# Power.net
KiCad netlist of a schematic drawn in Altium Designer
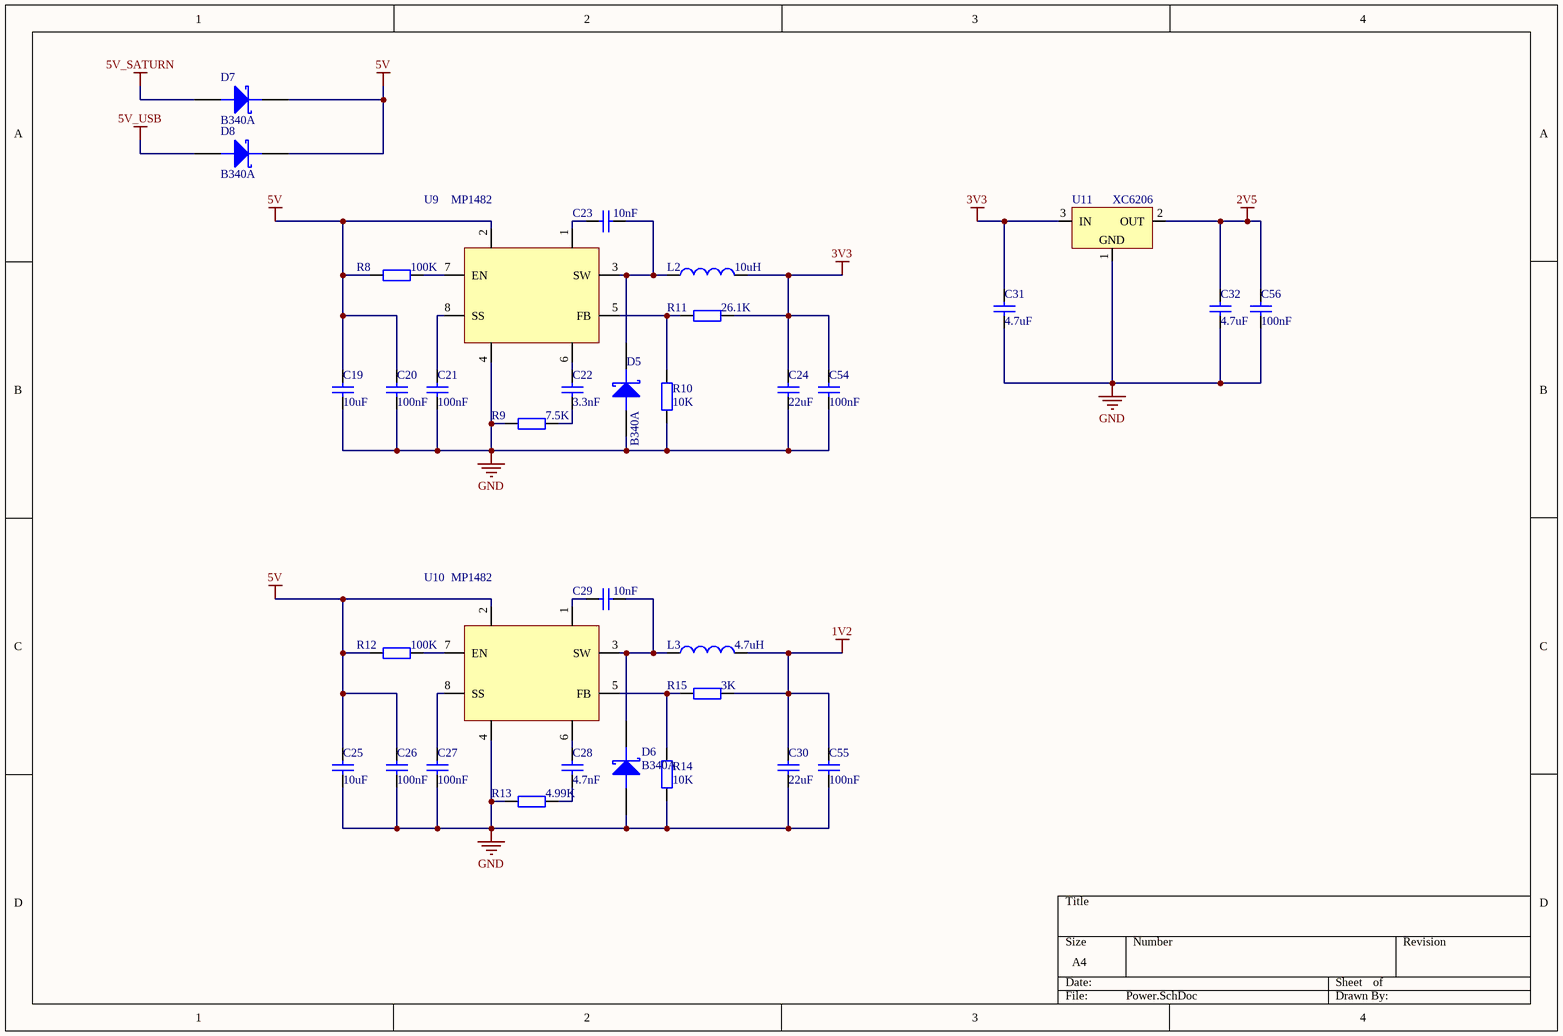
[diagram p0: Power.SchDoc]

(export (version "E")
  (design (tool "Eeschema 10.0.6"))
  (components
    (comp (ref "C19")
      (value "10uF")
      (footprint "C1206")
      (description "Capacitor")
      (fields (field (name "PUBLISHER") "Altium Limited"))
      (libsource (lib "Miscellaneous Devices") (part "Cap"))
    )
    (comp (ref "C20")
      (value "100nF")
      (footprint "C0603")
      (description "Capacitor")
      (fields (field (name "PUBLISHER") "Altium Limited"))
      (libsource (lib "Miscellaneous Devices") (part "Cap"))
    )
    (comp (ref "C21")
      (value "100nF")
      (footprint "C0603")
      (description "Capacitor")
      (fields (field (name "PUBLISHER") "Altium Limited"))
      (libsource (lib "Miscellaneous Devices") (part "Cap"))
    )
    (comp (ref "C22")
      (value "3.3nF")
      (footprint "C0603")
      (description "Capacitor")
      (fields (field (name "PUBLISHER") "Altium Limited"))
      (libsource (lib "Miscellaneous Devices") (part "Cap"))
    )
    (comp (ref "C23")
      (value "10nF")
      (footprint "C0603")
      (description "Capacitor")
      (fields (field (name "PUBLISHER") "Altium Limited"))
      (libsource (lib "Miscellaneous Devices") (part "Cap"))
    )
    (comp (ref "C24")
      (value "22uF")
      (footprint "C1206")
      (description "Capacitor")
      (fields (field (name "PUBLISHER") "Altium Limited"))
      (libsource (lib "Miscellaneous Devices") (part "Cap"))
    )
    (comp (ref "C25")
      (value "10uF")
      (footprint "C1206")
      (description "Capacitor")
      (fields (field (name "PUBLISHER") "Altium Limited"))
      (libsource (lib "Miscellaneous Devices") (part "Cap"))
    )
    (comp (ref "C26")
      (value "100nF")
      (footprint "C0603")
      (description "Capacitor")
      (fields (field (name "PUBLISHER") "Altium Limited"))
      (libsource (lib "Miscellaneous Devices") (part "Cap"))
    )
    (comp (ref "C27")
      (value "100nF")
      (footprint "C0603")
      (description "Capacitor")
      (fields (field (name "PUBLISHER") "Altium Limited"))
      (libsource (lib "Miscellaneous Devices") (part "Cap"))
    )
    (comp (ref "C28")
      (value "4.7nF")
      (footprint "C0603")
      (description "Capacitor")
      (fields (field (name "PUBLISHER") "Altium Limited"))
      (libsource (lib "Miscellaneous Devices") (part "Cap"))
    )
    (comp (ref "C29")
      (value "10nF")
      (footprint "C0603")
      (description "Capacitor")
      (fields (field (name "PUBLISHER") "Altium Limited"))
      (libsource (lib "Miscellaneous Devices") (part "Cap"))
    )
    (comp (ref "C30")
      (value "22uF")
      (footprint "C1206")
      (description "Capacitor")
      (fields (field (name "PUBLISHER") "Altium Limited"))
      (libsource (lib "Miscellaneous Devices") (part "Cap"))
    )
    (comp (ref "C31")
      (value "4.7uF")
      (footprint "C0603")
      (description "Capacitor")
      (fields (field (name "PUBLISHER") "Altium Limited"))
      (libsource (lib "Miscellaneous Devices") (part "Cap"))
    )
    (comp (ref "C32")
      (value "4.7uF")
      (footprint "C0603")
      (description "Capacitor")
      (fields (field (name "PUBLISHER") "Altium Limited"))
      (libsource (lib "Miscellaneous Devices") (part "Cap"))
    )
    (comp (ref "C54")
      (value "100nF")
      (footprint "C0603")
      (description "Capacitor")
      (fields (field (name "PUBLISHER") "Altium Limited"))
      (libsource (lib "Miscellaneous Devices") (part "Cap"))
    )
    (comp (ref "C55")
      (value "100nF")
      (footprint "C0603")
      (description "Capacitor")
      (fields (field (name "PUBLISHER") "Altium Limited"))
      (libsource (lib "Miscellaneous Devices") (part "Cap"))
    )
    (comp (ref "C56")
      (value "100nF")
      (footprint "C0603")
      (description "Capacitor")
      (fields (field (name "PUBLISHER") "Altium Limited"))
      (libsource (lib "Miscellaneous Devices") (part "Cap"))
    )
    (comp (ref "D5")
      (value "B340A")
      (footprint "SMA")
      (description "Schottky Diode")
      (libsource (lib "JL_SCH") (part "DIODE SCHOTTKY"))
    )
    (comp (ref "D6")
      (value "B340A")
      (footprint "SMA")
      (description "Schottky Diode")
      (libsource (lib "JL_SCH") (part "DIODE SCHOTTKY"))
    )
    (comp (ref "D7")
      (value "B340A")
      (footprint "SMA")
      (description "Schottky Diode")
      (libsource (lib "JL_SCH") (part "DIODE SCHOTTKY"))
    )
    (comp (ref "D8")
      (value "B340A")
      (footprint "SMA")
      (description "Schottky Diode")
      (libsource (lib "JL_SCH") (part "DIODE SCHOTTKY"))
    )
    (comp (ref "L2")
      (value "10uH")
      (footprint "CDRH5D28")
      (description "Inductor")
      (fields (field (name "PUBLISHER") "Altium Limited"))
      (libsource (lib "Miscellaneous Devices") (part "Inductor"))
    )
    (comp (ref "L3")
      (value "4.7uH")
      (footprint "CDRH5D28")
      (description "Inductor")
      (fields (field (name "PUBLISHER") "Altium Limited"))
      (libsource (lib "Miscellaneous Devices") (part "Inductor"))
    )
    (comp (ref "R8")
      (value "100K")
      (footprint "R0603")
      (description "Resistor")
      (fields (field (name "PUBLISHER") "Altium Limited"))
      (libsource (lib "") (part "Res2_1"))
    )
    (comp (ref "R9")
      (value "7.5K")
      (footprint "R0603")
      (description "Resistor")
      (fields (field (name "PUBLISHER") "Altium Limited"))
      (libsource (lib "") (part "Res2_1"))
    )
    (comp (ref "R10")
      (value "10K")
      (footprint "R0603")
      (description "Resistor")
      (fields (field (name "PUBLISHER") "Altium Limited"))
      (libsource (lib "Miscellaneous Devices") (part "Res2"))
    )
    (comp (ref "R11")
      (value "26.1K")
      (footprint "R0603")
      (description "Resistor")
      (fields (field (name "PUBLISHER") "Altium Limited"))
      (libsource (lib "") (part "Res2_1"))
    )
    (comp (ref "R12")
      (value "100K")
      (footprint "R0603")
      (description "Resistor")
      (fields (field (name "PUBLISHER") "Altium Limited"))
      (libsource (lib "") (part "Res2_1"))
    )
    (comp (ref "R13")
      (value "4.99K")
      (footprint "R0603")
      (description "Resistor")
      (fields (field (name "PUBLISHER") "Altium Limited"))
      (libsource (lib "") (part "Res2_1"))
    )
    (comp (ref "R14")
      (value "10K")
      (footprint "R0603")
      (description "Resistor")
      (fields (field (name "PUBLISHER") "Altium Limited"))
      (libsource (lib "Miscellaneous Devices") (part "Res2"))
    )
    (comp (ref "R15")
      (value "3K")
      (footprint "R0603")
      (description "Resistor")
      (fields (field (name "PUBLISHER") "Altium Limited"))
      (libsource (lib "") (part "Res2_1"))
    )
    (comp (ref "U9") (value "MP1482") (footprint "SOIC-8") (libsource (lib "ssmaster_1") (part "MP1482")))
    (comp (ref "U10") (value "MP1482") (footprint "SOIC-8") (libsource (lib "ssmaster_1") (part "MP1482")))
    (comp (ref "U11")
      (value "XC6206")
      (footprint "SOT-23")
      (description "LDO")
      (libsource (lib "ssmaster_1") (part "XC6206"))
    )
  )
  (nets
    (net (code "1") (name "1V2") (class "Default")
      (node (ref "C30") (pin "1") (pinfunction "1_1") (pintype "passive"))
      (node (ref "C55") (pin "2") (pinfunction "2_2") (pintype "passive"))
      (node (ref "L3") (pin "2") (pinfunction "2_2") (pintype "passive"))
      (node (ref "R15") (pin "1") (pinfunction "1_1") (pintype "passive"))
    )
    (net (code "2") (name "2V5") (class "Default")
      (node (ref "C32") (pin "2") (pinfunction "2_2") (pintype "passive"))
      (node (ref "C56") (pin "2") (pinfunction "2_2") (pintype "passive"))
      (node (ref "U11") (pin "2") (pinfunction "OUT_2") (pintype "power_in"))
    )
    (net (code "3") (name "3V3") (class "Default")
      (node (ref "C24") (pin "1") (pinfunction "1_1") (pintype "passive"))
      (node (ref "C31") (pin "2") (pinfunction "2_2") (pintype "passive"))
      (node (ref "C54") (pin "2") (pinfunction "2_2") (pintype "passive"))
      (node (ref "L2") (pin "2") (pinfunction "2_2") (pintype "passive"))
      (node (ref "R11") (pin "1") (pinfunction "1_1") (pintype "passive"))
      (node (ref "U11") (pin "3") (pinfunction "IN_3") (pintype "power_in"))
    )
    (net (code "4") (name "5V") (class "Default")
      (node (ref "C19") (pin "2") (pinfunction "2_2") (pintype "passive"))
      (node (ref "C20") (pin "2") (pinfunction "2_2") (pintype "passive"))
      (node (ref "C25") (pin "2") (pinfunction "2_2") (pintype "passive"))
      (node (ref "C26") (pin "2") (pinfunction "2_2") (pintype "passive"))
      (node (ref "D7") (pin "2") (pinfunction "K_2") (pintype "passive"))
      (node (ref "D8") (pin "2") (pinfunction "K_2") (pintype "passive"))
      (node (ref "R12") (pin "2") (pinfunction "2_2") (pintype "passive"))
      (node (ref "R8") (pin "2") (pinfunction "2_2") (pintype "passive"))
      (node (ref "U10") (pin "2") (pinfunction "IN_2") (pintype "power_in"))
      (node (ref "U9") (pin "2") (pinfunction "IN_2") (pintype "power_in"))
    )
    (net (code "5") (name "5V_SATURN") (class "Default")
      (node (ref "D7") (pin "1") (pinfunction "A_1") (pintype "passive"))
    )
    (net (code "6") (name "5V_USB") (class "Default")
      (node (ref "D8") (pin "1") (pinfunction "A_1") (pintype "passive"))
    )
    (net (code "7") (name "GND") (class "Default")
      (node (ref "C19") (pin "1") (pinfunction "1_1") (pintype "passive"))
      (node (ref "C20") (pin "1") (pinfunction "1_1") (pintype "passive"))
      (node (ref "C21") (pin "1") (pinfunction "1_1") (pintype "passive"))
      (node (ref "C24") (pin "2") (pinfunction "2_2") (pintype "passive"))
      (node (ref "C25") (pin "1") (pinfunction "1_1") (pintype "passive"))
      (node (ref "C26") (pin "1") (pinfunction "1_1") (pintype "passive"))
      (node (ref "C27") (pin "1") (pinfunction "1_1") (pintype "passive"))
      (node (ref "C30") (pin "2") (pinfunction "2_2") (pintype "passive"))
      (node (ref "C31") (pin "1") (pinfunction "1_1") (pintype "passive"))
      (node (ref "C32") (pin "1") (pinfunction "1_1") (pintype "passive"))
      (node (ref "C54") (pin "1") (pinfunction "1_1") (pintype "passive"))
      (node (ref "C55") (pin "1") (pinfunction "1_1") (pintype "passive"))
      (node (ref "C56") (pin "1") (pinfunction "1_1") (pintype "passive"))
      (node (ref "D5") (pin "1") (pinfunction "A_1") (pintype "passive"))
      (node (ref "D6") (pin "1") (pinfunction "A_1") (pintype "passive"))
      (node (ref "R10") (pin "1") (pinfunction "1_1") (pintype "passive"))
      (node (ref "R13") (pin "2") (pinfunction "2_2") (pintype "passive"))
      (node (ref "R14") (pin "1") (pinfunction "1_1") (pintype "passive"))
      (node (ref "R9") (pin "2") (pinfunction "2_2") (pintype "passive"))
      (node (ref "U10") (pin "4") (pinfunction "GND_4") (pintype "power_in"))
      (node (ref "U11") (pin "1") (pinfunction "GND_1") (pintype "power_in"))
      (node (ref "U9") (pin "4") (pinfunction "GND_4") (pintype "power_in"))
    )
    (net (code "8") (name "Net-(C22-Pad1)") (class "Default")
      (node (ref "C22") (pin "1") (pinfunction "1_1") (pintype "passive"))
      (node (ref "R9") (pin "1") (pinfunction "1_1") (pintype "passive"))
    )
    (net (code "9") (name "Net-(C28-Pad1)") (class "Default")
      (node (ref "C28") (pin "1") (pinfunction "1_1") (pintype "passive"))
      (node (ref "R13") (pin "1") (pinfunction "1_1") (pintype "passive"))
    )
    (net (code "10") (name "Net-(D5-K)") (class "Default")
      (node (ref "C23") (pin "1") (pinfunction "1_1") (pintype "passive"))
      (node (ref "D5") (pin "2") (pinfunction "K_2") (pintype "passive"))
      (node (ref "L2") (pin "1") (pinfunction "1_1") (pintype "passive"))
      (node (ref "U9") (pin "3") (pinfunction "SW_3") (pintype "passive"))
    )
    (net (code "11") (name "Net-(D6-K)") (class "Default")
      (node (ref "C29") (pin "1") (pinfunction "1_1") (pintype "passive"))
      (node (ref "D6") (pin "2") (pinfunction "K_2") (pintype "passive"))
      (node (ref "L3") (pin "1") (pinfunction "1_1") (pintype "passive"))
      (node (ref "U10") (pin "3") (pinfunction "SW_3") (pintype "passive"))
    )
    (net (code "12") (name "Net-(U9-BS)") (class "Default")
      (node (ref "C23") (pin "2") (pinfunction "2_2") (pintype "passive"))
      (node (ref "U9") (pin "1") (pinfunction "BS_1") (pintype "passive"))
    )
    (net (code "13") (name "Net-(U9-COMP)") (class "Default")
      (node (ref "C22") (pin "2") (pinfunction "2_2") (pintype "passive"))
      (node (ref "U9") (pin "6") (pinfunction "COMP_6") (pintype "passive"))
    )
    (net (code "14") (name "Net-(U9-EN)") (class "Default")
      (node (ref "R8") (pin "1") (pinfunction "1_1") (pintype "passive"))
      (node (ref "U9") (pin "7") (pinfunction "EN_7") (pintype "passive"))
    )
    (net (code "15") (name "Net-(U9-FB)") (class "Default")
      (node (ref "R10") (pin "2") (pinfunction "2_2") (pintype "passive"))
      (node (ref "R11") (pin "2") (pinfunction "2_2") (pintype "passive"))
      (node (ref "U9") (pin "5") (pinfunction "FB_5") (pintype "passive"))
    )
    (net (code "16") (name "Net-(U9-SS)") (class "Default")
      (node (ref "C21") (pin "2") (pinfunction "2_2") (pintype "passive"))
      (node (ref "U9") (pin "8") (pinfunction "SS_8") (pintype "passive"))
    )
    (net (code "17") (name "Net-(U10-BS)") (class "Default")
      (node (ref "C29") (pin "2") (pinfunction "2_2") (pintype "passive"))
      (node (ref "U10") (pin "1") (pinfunction "BS_1") (pintype "passive"))
    )
    (net (code "18") (name "Net-(U10-COMP)") (class "Default")
      (node (ref "C28") (pin "2") (pinfunction "2_2") (pintype "passive"))
      (node (ref "U10") (pin "6") (pinfunction "COMP_6") (pintype "passive"))
    )
    (net (code "19") (name "Net-(U10-EN)") (class "Default")
      (node (ref "R12") (pin "1") (pinfunction "1_1") (pintype "passive"))
      (node (ref "U10") (pin "7") (pinfunction "EN_7") (pintype "passive"))
    )
    (net (code "20") (name "Net-(U10-FB)") (class "Default")
      (node (ref "R14") (pin "2") (pinfunction "2_2") (pintype "passive"))
      (node (ref "R15") (pin "2") (pinfunction "2_2") (pintype "passive"))
      (node (ref "U10") (pin "5") (pinfunction "FB_5") (pintype "passive"))
    )
    (net (code "21") (name "Net-(U10-SS)") (class "Default")
      (node (ref "C27") (pin "2") (pinfunction "2_2") (pintype "passive"))
      (node (ref "U10") (pin "8") (pinfunction "SS_8") (pintype "passive"))
    )
  )
)
